# heater-pwm-logic.net
KiCad netlist of a schematic drawn in Altium Designer
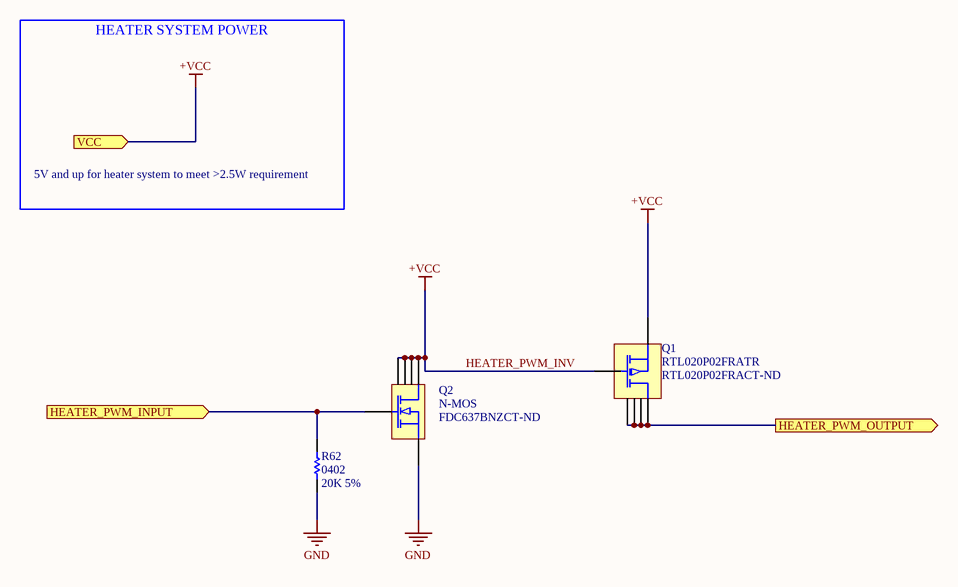
[diagram p0: heater-pwm-logic.SchDoc]

(export (version "E")
  (design (tool "Eeschema 10.0.6"))
  (components
    (comp (ref "Q1")
      (value "RTL020P02FRATR")
      (footprint "SOT95P280X145-6N")
      (description "2.5V DRIVE PCH MOSFET, AEC-Q101, 20V 2A (Ta) 1W (Ta) Surface Mount TUMT6")
      (fields (field (name "SUPPLIER PART NUMBER 1") "RTL020P02FRACT-ND"))
      (libsource (lib "RTL020P02FRATR") (part "RTL020P02FRATR"))
    )
    (comp (ref "Q2")
      (value "N-MOS")
      (footprint "SOT95P280X145-6N")
      (description "20V 6.2A, N-MOS, low gate on voltage")
      (fields (field (name "SUPPLIER PART NUMBER 1") "FDC637BNZCT-ND"))
      (libsource (lib "heron-general") (part "FDC637BNZCT-ND"))
    )
    (comp (ref "R62")
      (value "0402")
      (footprint "RES0402R")
      (description "0402 resistor")
      (fields (field (name "ALTIUM_VALUE") "20K 5%"))
      (libsource (lib "RES0402") (part "RES0402"))
    )
  )
  (nets
    (net (code "1") (name "+VCC") (class "Default")
      (node (ref "Q1") (pin "3") (pinfunction "G_3") (pintype "passive"))
      (node (ref "Q1") (pin "4") (pinfunction "S_4") (pintype "passive"))
      (node (ref "Q2") (pin "1") (pinfunction "D_1") (pintype "passive"))
      (node (ref "Q2") (pin "2") (pinfunction "D_2") (pintype "passive"))
      (node (ref "Q2") (pin "5") (pinfunction "D_5") (pintype "passive"))
      (node (ref "Q2") (pin "6") (pinfunction "D_6") (pintype "passive"))
    )
    (net (code "2") (name "/HEATER_PWM_INPUT") (class "Default")
      (node (ref "Q2") (pin "3") (pinfunction "G_3") (pintype "passive"))
      (node (ref "R62") (pin "2") (pinfunction "2_2") (pintype "passive"))
    )
    (net (code "3") (name "/HEATER_PWM_OUTPUT") (class "Default")
      (node (ref "Q1") (pin "1") (pinfunction "D_1") (pintype "passive"))
      (node (ref "Q1") (pin "2") (pinfunction "D_2") (pintype "passive"))
      (node (ref "Q1") (pin "5") (pinfunction "D_5") (pintype "passive"))
      (node (ref "Q1") (pin "6") (pinfunction "D_6") (pintype "passive"))
    )
    (net (code "4") (name "GND") (class "Default")
      (node (ref "Q2") (pin "4") (pinfunction "S_4") (pintype "passive"))
      (node (ref "R62") (pin "1") (pinfunction "1_1") (pintype "passive"))
    )
  )
)
